# Sheet2.net
KiCad netlist of a schematic drawn in Altium Designer
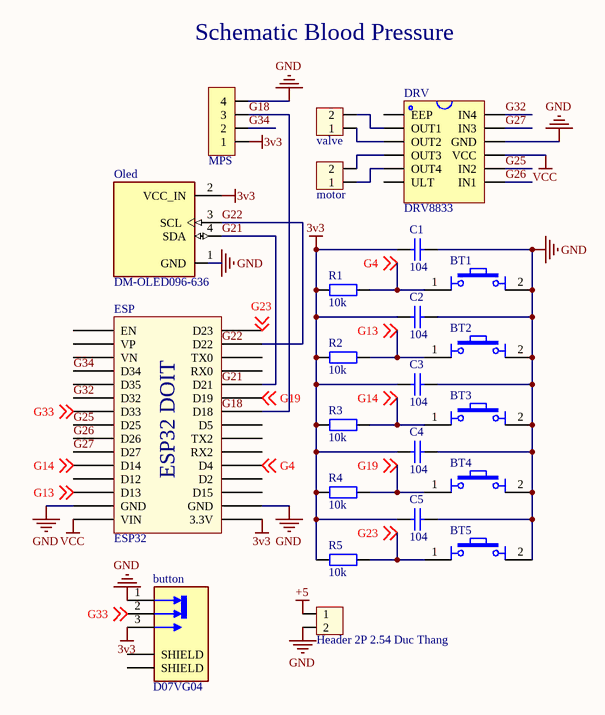
[diagram p0: Sheet2.SchDoc]

(export (version "E")
  (design (tool "Eeschema 10.0.6"))
  (components
    (comp (ref "BT1")
      (value "~")
      (footprint "Nut Nhan 4 Chan Cam 6x6")
      (description "Nut Nhan 4 Chan 6x6mm")
      (libsource (lib "Altium_Lib_by_KhueNguyenCreator") (part "Nut Nhan 4 Chan Cam 6x6"))
    )
    (comp (ref "BT2")
      (value "~")
      (footprint "Nut Nhan 4 Chan Cam 6x6")
      (description "Nut Nhan 4 Chan 6x6mm")
      (libsource (lib "Altium_Lib_by_KhueNguyenCreator") (part "Nut Nhan 4 Chan Cam 6x6"))
    )
    (comp (ref "BT3")
      (value "~")
      (footprint "Nut Nhan 4 Chan Cam 6x6")
      (description "Nut Nhan 4 Chan 6x6mm")
      (libsource (lib "Altium_Lib_by_KhueNguyenCreator") (part "Nut Nhan 4 Chan Cam 6x6"))
    )
    (comp (ref "BT4")
      (value "~")
      (footprint "Nut Nhan 4 Chan Cam 6x6")
      (description "Nut Nhan 4 Chan 6x6mm")
      (libsource (lib "Altium_Lib_by_KhueNguyenCreator") (part "Nut Nhan 4 Chan Cam 6x6"))
    )
    (comp (ref "BT5")
      (value "~")
      (footprint "Nut Nhan 4 Chan Cam 6x6")
      (description "Nut Nhan 4 Chan 6x6mm")
      (libsource (lib "Altium_Lib_by_KhueNguyenCreator") (part "Nut Nhan 4 Chan Cam 6x6"))
    )
    (comp (ref "button")
      (value "D07VG04")
      (footprint "SW_SS12D07VG4")
      (description "Switch Slide ON ON SPDT Top Slide 0.3A 30VDC PC Pins Bracket Mount/Through Hole Automotive Bulk")
      (fields (field (name "MF") "Shouhan") (field (name "MP") "SS12D07VG4"))
      (libsource (lib "SS12D07VG4") (part "SS12D07VG4"))
    )
    (comp (ref "C1")
      (value "104")
      (footprint "tu 0805")
      (description "Dán")
      (libsource (lib "Altium_Lib_by_KhueNguyenCreator") (part "Tu 0805 104 50V 10%"))
    )
    (comp (ref "C2")
      (value "104")
      (footprint "tu 0805")
      (description "Dán")
      (libsource (lib "Altium_Lib_by_KhueNguyenCreator") (part "Tu 0805 104 50V 10%"))
    )
    (comp (ref "C3")
      (value "104")
      (footprint "tu 0805")
      (description "Dán")
      (libsource (lib "Altium_Lib_by_KhueNguyenCreator") (part "Tu 0805 104 50V 10%"))
    )
    (comp (ref "C4")
      (value "104")
      (footprint "tu 0805")
      (description "Dán")
      (libsource (lib "Altium_Lib_by_KhueNguyenCreator") (part "Tu 0805 104 50V 10%"))
    )
    (comp (ref "C5")
      (value "104")
      (footprint "tu 0805")
      (description "Dán")
      (libsource (lib "Altium_Lib_by_KhueNguyenCreator") (part "Tu 0805 104 50V 10%"))
    )
    (comp (ref "DRV") (value "DRV8833") (footprint "DRV8833") (libsource (lib "lib") (part "DRV8833")))
    (comp (ref "ESP")
      (value "ESP32")
      (footprint "ESP32 WROOM 32 KIT")
      (libsource (lib "Altium_Lib_by_KhueNguyenCreator") (part "ESP32 WROOM 32 KIT"))
    )
    (comp (ref "motor")
      (value "motor")
      (footprint "XH2.54M-2")
      (description "Cắm")
      (libsource (lib "") (part "Header 2P 2.54 Duc Thang_1"))
    )
    (comp (ref "Mps")
      (value "MPS")
      (footprint "JP 1x4 CT")
      (description "Cắm")
      (libsource (lib "lib") (part "JP 1x4 2.54 Cai Thang"))
    )
    (comp (ref "Oled")
      (value "DM-OLED096-636")
      (footprint "MODULE_DM-OLED096-636")
      (description "0.96â€ 128 X 64 MONOCHROME GRAPHIC OLED DISPLAY MODULE - I2C")
      (fields (field (name "MF") "Display Module"))
      (libsource (lib "DM-OLED096-636") (part "DM-OLED096-636"))
    )
    (comp (ref "Pin")
      (value "Header 2P 2.54 Duc Thang")
      (footprint "XH2.54M-2")
      (description "Cắm")
      (libsource (lib "lib") (part "Header 2P 2.54 Duc Thang"))
    )
    (comp (ref "R1")
      (value "10k")
      (footprint "tro smd 0805")
      (description "Dán")
      (libsource (lib "lib") (part "Tro 0805 1% 10k"))
    )
    (comp (ref "R2")
      (value "10k")
      (footprint "tro smd 0805")
      (description "Dán")
      (libsource (lib "lib") (part "Tro 0805 1% 10k"))
    )
    (comp (ref "R3")
      (value "10k")
      (footprint "tro smd 0805")
      (description "Dán")
      (libsource (lib "lib") (part "Tro 0805 1% 10k"))
    )
    (comp (ref "R4")
      (value "10k")
      (footprint "tro smd 0805")
      (description "Dán")
      (libsource (lib "lib") (part "Tro 0805 1% 10k"))
    )
    (comp (ref "R5")
      (value "10k")
      (footprint "tro smd 0805")
      (description "Dán")
      (libsource (lib "lib") (part "Tro 0805 1% 10k"))
    )
    (comp (ref "valve")
      (value "valve")
      (footprint "XH2.54M-2")
      (description "Cắm")
      (libsource (lib "") (part "Header 2P 2.54 Duc Thang_1"))
    )
  )
  (nets
    (net (code "1") (name "+5") (class "Default")
      (node (ref "Pin") (pin "1") (pinfunction "1_1") (pintype "passive"))
    )
    (net (code "2") (name "/G18") (class "Default")
      (node (ref "ESP") (pin "24") (pinfunction "D18_24") (pintype "passive"))
      (node (ref "Mps") (pin "3") (pinfunction "3_3") (pintype "passive"))
    )
    (net (code "3") (name "/G21") (class "Default")
      (node (ref "ESP") (pin "26") (pinfunction "D21_26") (pintype "passive"))
      (node (ref "Oled") (pin "4") (pinfunction "SDA_4") (pintype "bidirectional"))
    )
    (net (code "4") (name "/G22") (class "Default")
      (node (ref "ESP") (pin "29") (pinfunction "D22_29") (pintype "passive"))
      (node (ref "Oled") (pin "3") (pinfunction "SCL_3") (pintype "input"))
    )
    (net (code "5") (name "/G25") (class "Default")
      (node (ref "DRV") (pin "8") (pinfunction "IN2_8") (pintype "passive"))
      (node (ref "ESP") (pin "8") (pinfunction "D25_8") (pintype "passive"))
    )
    (net (code "6") (name "/G26") (class "Default")
      (node (ref "DRV") (pin "7") (pinfunction "IN1_7") (pintype "passive"))
      (node (ref "ESP") (pin "9") (pinfunction "D26_9") (pintype "passive"))
    )
    (net (code "7") (name "/G27") (class "Default")
      (node (ref "DRV") (pin "11") (pinfunction "IN3_11") (pintype "passive"))
      (node (ref "ESP") (pin "10") (pinfunction "D27_10") (pintype "passive"))
    )
    (net (code "8") (name "/G32") (class "Default")
      (node (ref "DRV") (pin "12") (pinfunction "IN4_12") (pintype "passive"))
      (node (ref "ESP") (pin "6") (pinfunction "D32_6") (pintype "passive"))
    )
    (net (code "9") (name "/G34") (class "Default")
      (node (ref "ESP") (pin "4") (pinfunction "D34_4") (pintype "passive"))
      (node (ref "Mps") (pin "2") (pinfunction "2_2") (pintype "passive"))
    )
    (net (code "10") (name "3v3") (class "Default")
      (node (ref "C1") (pin "2") (pinfunction "2_2") (pintype "passive"))
      (node (ref "C2") (pin "2") (pinfunction "2_2") (pintype "passive"))
      (node (ref "C3") (pin "2") (pinfunction "2_2") (pintype "passive"))
      (node (ref "C4") (pin "2") (pinfunction "2_2") (pintype "passive"))
      (node (ref "C5") (pin "2") (pinfunction "2_2") (pintype "passive"))
      (node (ref "ESP") (pin "16") (pinfunction "3.3V_16") (pintype "passive"))
      (node (ref "Mps") (pin "1") (pinfunction "1_1") (pintype "passive"))
      (node (ref "Oled") (pin "2") (pinfunction "VCC_IN_2") (pintype "power_in"))
      (node (ref "R1") (pin "1") (pinfunction "1_1") (pintype "passive"))
      (node (ref "R2") (pin "1") (pinfunction "1_1") (pintype "passive"))
      (node (ref "R3") (pin "1") (pinfunction "1_1") (pintype "passive"))
      (node (ref "R4") (pin "1") (pinfunction "1_1") (pintype "passive"))
      (node (ref "R5") (pin "1") (pinfunction "1_1") (pintype "passive"))
      (node (ref "button") (pin "3") (pinfunction "3_3") (pintype "passive"))
    )
    (net (code "11") (name "G4") (class "Default")
      (node (ref "BT1") (pin "1") (pintype "passive"))
      (node (ref "ESP") (pin "20") (pinfunction "D4_20") (pintype "passive"))
      (node (ref "R1") (pin "2") (pinfunction "2_2") (pintype "passive"))
    )
    (net (code "12") (name "G13") (class "Default")
      (node (ref "BT2") (pin "1") (pintype "passive"))
      (node (ref "ESP") (pin "13") (pinfunction "D13_13") (pintype "passive"))
      (node (ref "R2") (pin "2") (pinfunction "2_2") (pintype "passive"))
    )
    (net (code "13") (name "G14") (class "Default")
      (node (ref "BT3") (pin "1") (pintype "passive"))
      (node (ref "ESP") (pin "11") (pinfunction "D14_11") (pintype "passive"))
      (node (ref "R3") (pin "2") (pinfunction "2_2") (pintype "passive"))
    )
    (net (code "14") (name "G19") (class "Default")
      (node (ref "BT4") (pin "1") (pintype "passive"))
      (node (ref "ESP") (pin "25") (pinfunction "D19_25") (pintype "passive"))
      (node (ref "R4") (pin "2") (pinfunction "2_2") (pintype "passive"))
    )
    (net (code "15") (name "G23") (class "Default")
      (node (ref "BT5") (pin "1") (pintype "passive"))
      (node (ref "ESP") (pin "30") (pinfunction "D23_30") (pintype "passive"))
      (node (ref "R5") (pin "2") (pinfunction "2_2") (pintype "passive"))
    )
    (net (code "16") (name "G33") (class "Default")
      (node (ref "ESP") (pin "7") (pinfunction "D33_7") (pintype "passive"))
      (node (ref "button") (pin "2") (pinfunction "2_2") (pintype "passive"))
    )
    (net (code "17") (name "GND") (class "Default")
      (node (ref "BT1") (pin "2") (pintype "passive"))
      (node (ref "BT2") (pin "2") (pintype "passive"))
      (node (ref "BT3") (pin "2") (pintype "passive"))
      (node (ref "BT4") (pin "2") (pintype "passive"))
      (node (ref "BT5") (pin "2") (pintype "passive"))
      (node (ref "C1") (pin "1") (pinfunction "1_1") (pintype "passive"))
      (node (ref "C2") (pin "1") (pinfunction "1_1") (pintype "passive"))
      (node (ref "C3") (pin "1") (pinfunction "1_1") (pintype "passive"))
      (node (ref "C4") (pin "1") (pinfunction "1_1") (pintype "passive"))
      (node (ref "C5") (pin "1") (pinfunction "1_1") (pintype "passive"))
      (node (ref "DRV") (pin "10") (pinfunction "GND_10") (pintype "passive"))
      (node (ref "ESP") (pin "14") (pinfunction "GND_14") (pintype "passive"))
      (node (ref "ESP") (pin "17") (pinfunction "GND_17") (pintype "passive"))
      (node (ref "Mps") (pin "4") (pinfunction "4_4") (pintype "passive"))
      (node (ref "Oled") (pin "1") (pinfunction "GND_1") (pintype "power_in"))
      (node (ref "Pin") (pin "2") (pinfunction "2_2") (pintype "passive"))
      (node (ref "button") (pin "1") (pinfunction "1_1") (pintype "passive"))
    )
    (net (code "18") (name "Net-(DRV-OUT1)") (class "Default")
      (node (ref "DRV") (pin "2") (pinfunction "OUT1_2") (pintype "passive"))
      (node (ref "valve") (pin "2") (pinfunction "2_2") (pintype "passive"))
    )
    (net (code "19") (name "Net-(DRV-OUT2)") (class "Default")
      (node (ref "DRV") (pin "3") (pinfunction "OUT2_3") (pintype "passive"))
      (node (ref "valve") (pin "1") (pinfunction "1_1") (pintype "passive"))
    )
    (net (code "20") (name "Net-(DRV-OUT3)") (class "Default")
      (node (ref "DRV") (pin "4") (pinfunction "OUT3_4") (pintype "passive"))
      (node (ref "motor") (pin "2") (pinfunction "2_2") (pintype "passive"))
    )
    (net (code "21") (name "Net-(DRV-OUT4)") (class "Default")
      (node (ref "DRV") (pin "5") (pinfunction "OUT4_5") (pintype "passive"))
      (node (ref "motor") (pin "1") (pinfunction "1_1") (pintype "passive"))
    )
    (net (code "22") (name "VCC") (class "Default")
      (node (ref "DRV") (pin "9") (pinfunction "VCC_9") (pintype "passive"))
      (node (ref "ESP") (pin "15") (pinfunction "VIN_15") (pintype "passive"))
    )
    (net (code "23") (name "unconnected-(DRV-EEP-Pad1)") (class "Default")
      (node (ref "DRV") (pin "1") (pinfunction "EEP_1") (pintype "passive"))
    )
    (net (code "24") (name "unconnected-(DRV-ULT-Pad6)") (class "Default")
      (node (ref "DRV") (pin "6") (pinfunction "ULT_6") (pintype "passive"))
    )
    (net (code "25") (name "unconnected-(ESP-D2-Pad19)") (class "Default")
      (node (ref "ESP") (pin "19") (pinfunction "D2_19") (pintype "passive"))
    )
    (net (code "26") (name "unconnected-(ESP-D5-Pad23)") (class "Default")
      (node (ref "ESP") (pin "23") (pinfunction "D5_23") (pintype "passive"))
    )
    (net (code "27") (name "unconnected-(ESP-D12-Pad12)") (class "Default")
      (node (ref "ESP") (pin "12") (pinfunction "D12_12") (pintype "passive"))
    )
    (net (code "28") (name "unconnected-(ESP-D15-Pad18)") (class "Default")
      (node (ref "ESP") (pin "18") (pinfunction "D15_18") (pintype "passive"))
    )
    (net (code "29") (name "unconnected-(ESP-D35-Pad5)") (class "Default")
      (node (ref "ESP") (pin "5") (pinfunction "D35_5") (pintype "passive"))
    )
    (net (code "30") (name "unconnected-(ESP-EN-Pad1)") (class "Default")
      (node (ref "ESP") (pin "1") (pinfunction "EN_1") (pintype "passive"))
    )
    (net (code "31") (name "unconnected-(ESP-RX0-Pad27)") (class "Default")
      (node (ref "ESP") (pin "27") (pinfunction "RX0_27") (pintype "passive"))
    )
    (net (code "32") (name "unconnected-(ESP-RX2-Pad21)") (class "Default")
      (node (ref "ESP") (pin "21") (pinfunction "RX2_21") (pintype "passive"))
    )
    (net (code "33") (name "unconnected-(ESP-TX0-Pad28)") (class "Default")
      (node (ref "ESP") (pin "28") (pinfunction "TX0_28") (pintype "passive"))
    )
    (net (code "34") (name "unconnected-(ESP-TX2-Pad22)") (class "Default")
      (node (ref "ESP") (pin "22") (pinfunction "TX2_22") (pintype "passive"))
    )
    (net (code "35") (name "unconnected-(ESP-VN-Pad3)") (class "Default")
      (node (ref "ESP") (pin "3") (pinfunction "VN_3") (pintype "passive"))
    )
    (net (code "36") (name "unconnected-(ESP-VP-Pad2)") (class "Default")
      (node (ref "ESP") (pin "2") (pinfunction "VP_2") (pintype "passive"))
    )
    (net (code "37") (name "unconnected-(button-SHIELD-PadS1)") (class "Default")
      (node (ref "button") (pin "S1") (pinfunction "SHIELD_S1") (pintype "passive"))
    )
    (net (code "38") (name "unconnected-(button-SHIELD-PadS2)") (class "Default")
      (node (ref "button") (pin "S2") (pinfunction "SHIELD_S2") (pintype "passive"))
    )
  )
)
